# 150223_AriloRX_REV2_0_0.net
KiCad netlist of a schematic drawn in EAGLE
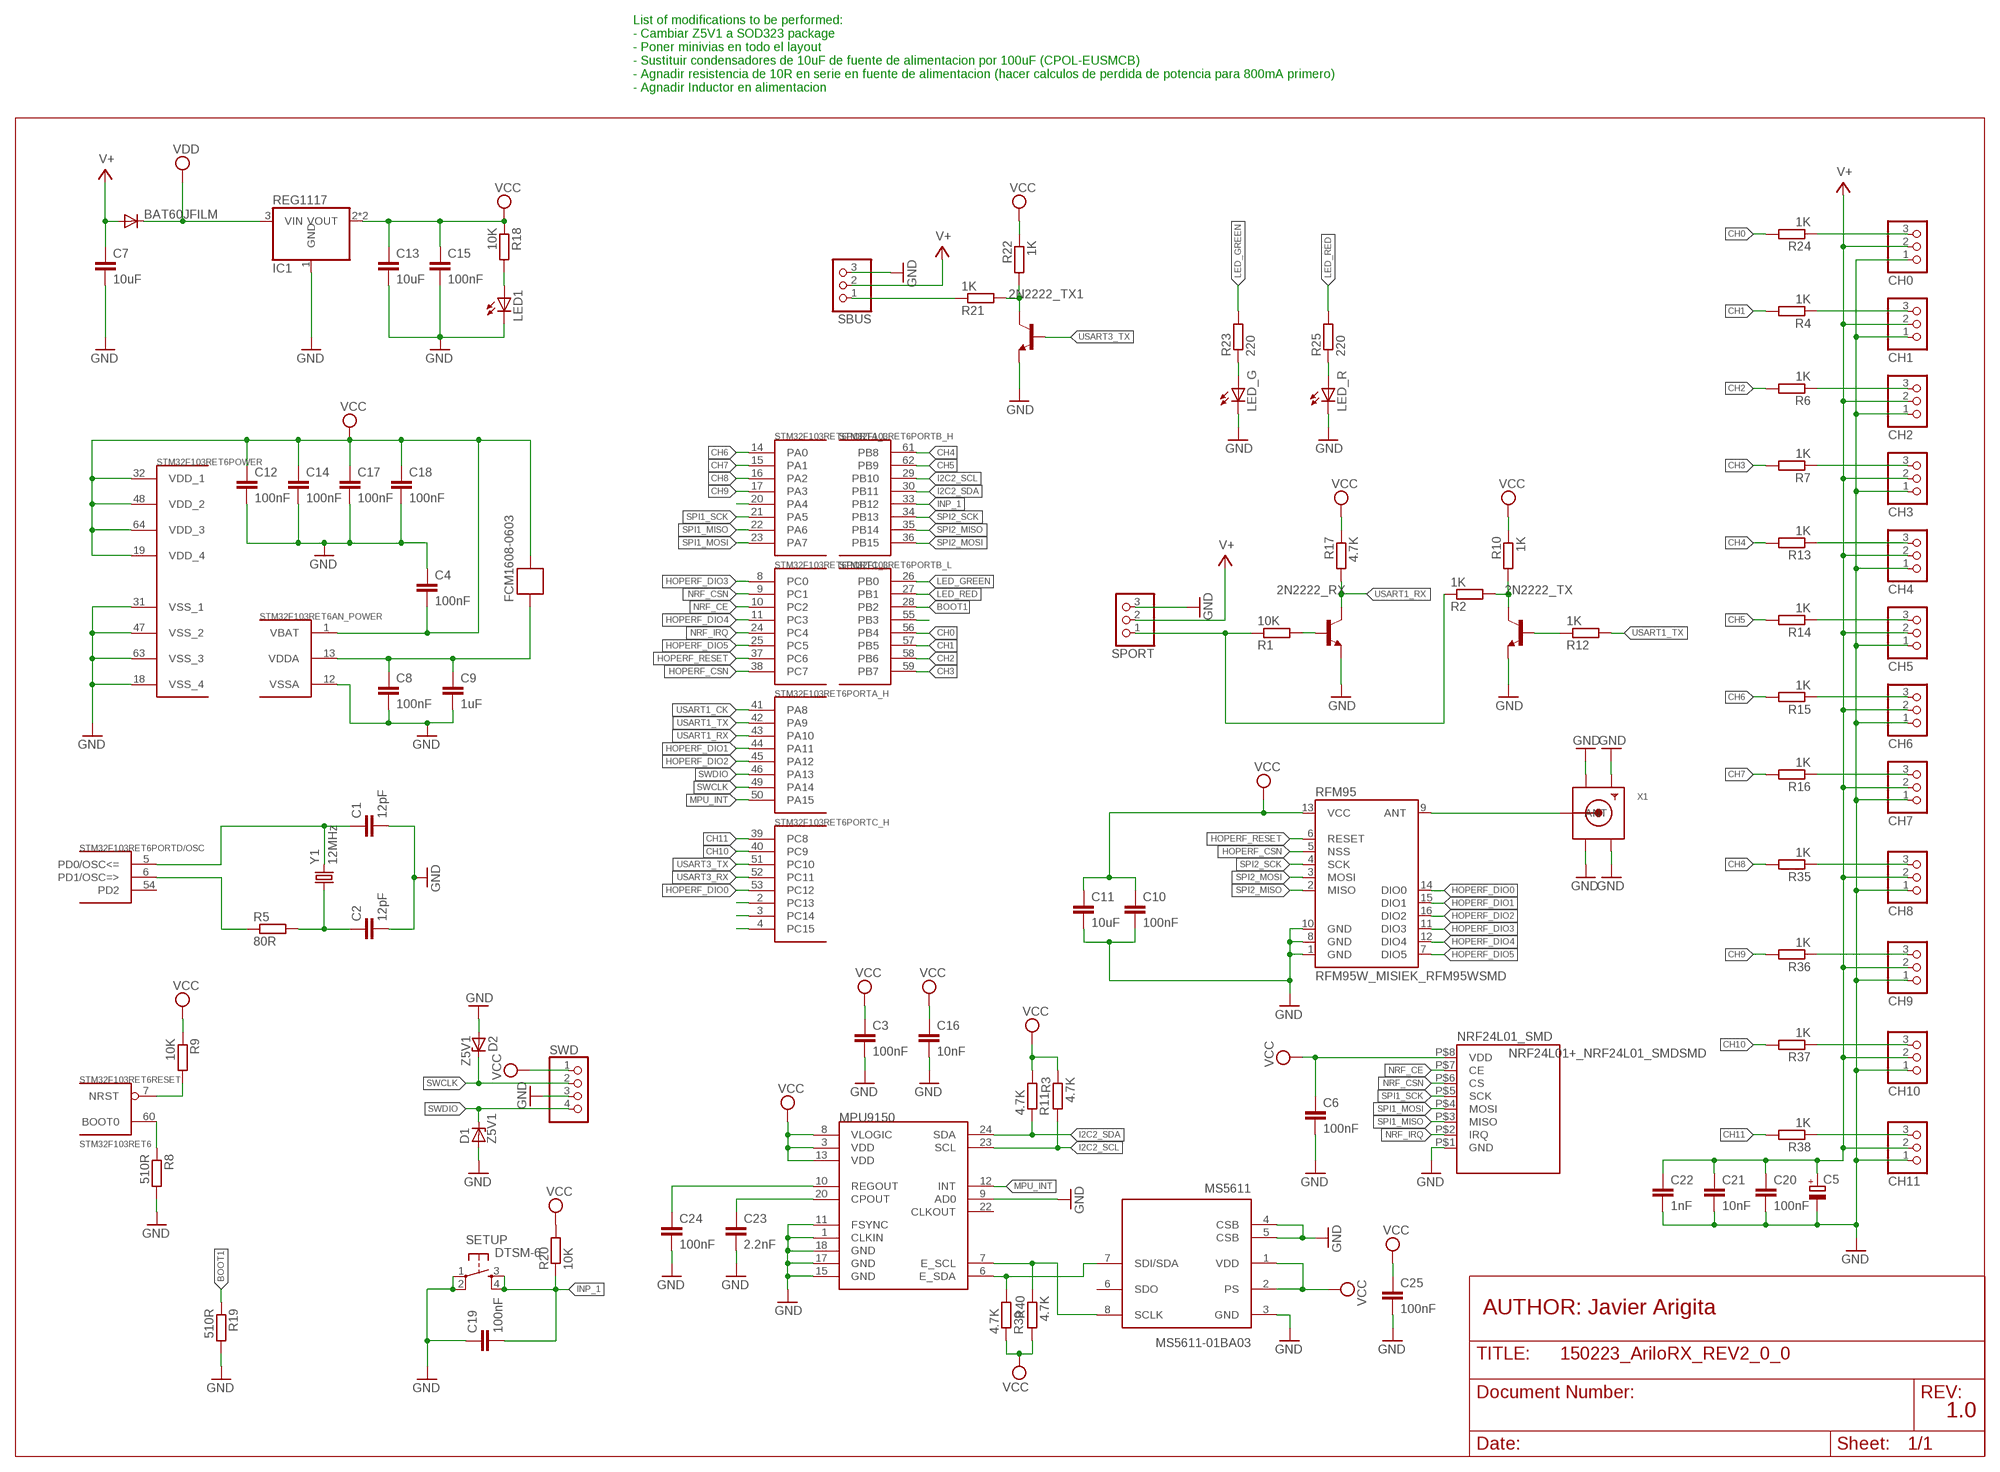
[diagram p0: schematic, sheet 1]

(export (version "E")
  (design (tool "Eeschema 10.0.6"))
  (components
    (comp (ref "2N2222_RX")
      (value "MMBT2222ALT1-NPN-SOT23-BEC")
      (footprint "eagle-import:SOT23-BEC")
      (libsource (lib "eagle-import") (part "-NPN-SOT23-BECMMBT2222ALT1"))
    )
    (comp (ref "2N2222_TX")
      (value "MMBT2222ALT1-NPN-SOT23-BEC")
      (footprint "eagle-import:SOT23-BEC")
      (libsource (lib "eagle-import") (part "-NPN-SOT23-BECMMBT2222ALT1"))
    )
    (comp (ref "2N2222_TX1")
      (value "MMBT2222ALT1-NPN-SOT23-BEC")
      (footprint "eagle-import:SOT23-BEC")
      (libsource (lib "eagle-import") (part "-NPN-SOT23-BECMMBT2222ALT1"))
    )
    (comp (ref "BAT60JFILM")
      (value "DIODE-SOD323-R")
      (footprint "eagle-import:SOD323-R")
      (libsource (lib "eagle-import") (part "DIODE-SOD323-R"))
    )
    (comp (ref "C1")
      (value "12pF")
      (footprint "eagle-import:RESISTOR_C0603")
      (libsource (lib "eagle-import") (part "RESISTOR_C-EUC0603"))
    )
    (comp (ref "C2")
      (value "12pF")
      (footprint "eagle-import:RESISTOR_C0603")
      (libsource (lib "eagle-import") (part "RESISTOR_C-EUC0603"))
    )
    (comp (ref "C3")
      (value "100nF")
      (footprint "eagle-import:RESISTOR_C0603")
      (libsource (lib "eagle-import") (part "RESISTOR_C-EUC0603"))
    )
    (comp (ref "C4")
      (value "100nF")
      (footprint "eagle-import:RESISTOR_C0603")
      (libsource (lib "eagle-import") (part "RESISTOR_C-EUC0603"))
    )
    (comp (ref "C5")
      (value "CPOL-EUSMCB")
      (footprint "eagle-import:SMC_B")
      (libsource (lib "eagle-import") (part "CPOL-EUSMCB"))
    )
    (comp (ref "C6")
      (value "100nF")
      (footprint "eagle-import:RESISTOR_C0603")
      (libsource (lib "eagle-import") (part "RESISTOR_C-EUC0603"))
    )
    (comp (ref "C7")
      (value "10uF")
      (footprint "eagle-import:RESISTOR_C3216")
      (libsource (lib "eagle-import") (part "RESISTOR_C-EUC3216"))
    )
    (comp (ref "C8")
      (value "100nF")
      (footprint "eagle-import:RESISTOR_C0603")
      (libsource (lib "eagle-import") (part "RESISTOR_C-EUC0603"))
    )
    (comp (ref "C9")
      (value "1uF")
      (footprint "eagle-import:RESISTOR_C0603")
      (libsource (lib "eagle-import") (part "RESISTOR_C-EUC0603"))
    )
    (comp (ref "C10")
      (value "100nF")
      (footprint "eagle-import:RESISTOR_C0603")
      (libsource (lib "eagle-import") (part "RESISTOR_C-EUC0603"))
    )
    (comp (ref "C11")
      (value "10uF")
      (footprint "eagle-import:RESISTOR_C3216")
      (libsource (lib "eagle-import") (part "RESISTOR_C-EUC3216"))
    )
    (comp (ref "C12")
      (value "100nF")
      (footprint "eagle-import:RESISTOR_C0603")
      (libsource (lib "eagle-import") (part "RESISTOR_C-EUC0603"))
    )
    (comp (ref "C13")
      (value "10uF")
      (footprint "eagle-import:RESISTOR_C3216")
      (libsource (lib "eagle-import") (part "RESISTOR_C-EUC3216"))
    )
    (comp (ref "C14")
      (value "100nF")
      (footprint "eagle-import:RESISTOR_C0603")
      (libsource (lib "eagle-import") (part "RESISTOR_C-EUC0603"))
    )
    (comp (ref "C15")
      (value "100nF")
      (footprint "eagle-import:RESISTOR_C0603")
      (libsource (lib "eagle-import") (part "RESISTOR_C-EUC0603"))
    )
    (comp (ref "C16")
      (value "10nF")
      (footprint "eagle-import:RESISTOR_C0603")
      (libsource (lib "eagle-import") (part "RESISTOR_C-EUC0603"))
    )
    (comp (ref "C17")
      (value "100nF")
      (footprint "eagle-import:RESISTOR_C0603")
      (libsource (lib "eagle-import") (part "RESISTOR_C-EUC0603"))
    )
    (comp (ref "C18")
      (value "100nF")
      (footprint "eagle-import:RESISTOR_C0603")
      (libsource (lib "eagle-import") (part "RESISTOR_C-EUC0603"))
    )
    (comp (ref "C19")
      (value "100nF")
      (footprint "eagle-import:RESISTOR_C0603")
      (libsource (lib "eagle-import") (part "RESISTOR_C-EUC0603"))
    )
    (comp (ref "C20")
      (value "100nF")
      (footprint "eagle-import:RESISTOR_C0603")
      (libsource (lib "eagle-import") (part "RESISTOR_C-EUC0603"))
    )
    (comp (ref "C21")
      (value "10nF")
      (footprint "eagle-import:RESISTOR_C0603")
      (libsource (lib "eagle-import") (part "RESISTOR_C-EUC0603"))
    )
    (comp (ref "C22")
      (value "1nF")
      (footprint "eagle-import:RESISTOR_C0603")
      (libsource (lib "eagle-import") (part "RESISTOR_C-EUC0603"))
    )
    (comp (ref "C23")
      (value "2.2nF")
      (footprint "eagle-import:RESISTOR_C0603")
      (libsource (lib "eagle-import") (part "RESISTOR_C-EUC0603"))
    )
    (comp (ref "C24")
      (value "100nF")
      (footprint "eagle-import:RESISTOR_C0603")
      (libsource (lib "eagle-import") (part "RESISTOR_C-EUC0603"))
    )
    (comp (ref "C25")
      (value "100nF")
      (footprint "eagle-import:RESISTOR_C0603")
      (libsource (lib "eagle-import") (part "RESISTOR_C-EUC0603"))
    )
    (comp (ref "CH0")
      (value "PINHD-1X3")
      (footprint "eagle-import:1X03")
      (libsource (lib "eagle-import") (part "PINHD-1X3"))
    )
    (comp (ref "CH1")
      (value "PINHD-1X3")
      (footprint "eagle-import:1X03")
      (libsource (lib "eagle-import") (part "PINHD-1X3"))
    )
    (comp (ref "CH2")
      (value "PINHD-1X3")
      (footprint "eagle-import:1X03")
      (libsource (lib "eagle-import") (part "PINHD-1X3"))
    )
    (comp (ref "CH3")
      (value "PINHD-1X3")
      (footprint "eagle-import:1X03")
      (libsource (lib "eagle-import") (part "PINHD-1X3"))
    )
    (comp (ref "CH4")
      (value "PINHD-1X3")
      (footprint "eagle-import:1X03")
      (libsource (lib "eagle-import") (part "PINHD-1X3"))
    )
    (comp (ref "CH5")
      (value "PINHD-1X3")
      (footprint "eagle-import:1X03")
      (libsource (lib "eagle-import") (part "PINHD-1X3"))
    )
    (comp (ref "CH6")
      (value "PINHD-1X3")
      (footprint "eagle-import:1X03")
      (libsource (lib "eagle-import") (part "PINHD-1X3"))
    )
    (comp (ref "CH7")
      (value "PINHD-1X3")
      (footprint "eagle-import:1X03")
      (libsource (lib "eagle-import") (part "PINHD-1X3"))
    )
    (comp (ref "CH8")
      (value "PINHD-1X3")
      (footprint "eagle-import:1X03")
      (libsource (lib "eagle-import") (part "PINHD-1X3"))
    )
    (comp (ref "CH9")
      (value "PINHD-1X3")
      (footprint "eagle-import:1X03")
      (libsource (lib "eagle-import") (part "PINHD-1X3"))
    )
    (comp (ref "CH10")
      (value "PINHD-1X3")
      (footprint "eagle-import:1X03")
      (libsource (lib "eagle-import") (part "PINHD-1X3"))
    )
    (comp (ref "CH11")
      (value "PINHD-1X3")
      (footprint "eagle-import:1X03")
      (libsource (lib "eagle-import") (part "PINHD-1X3"))
    )
    (comp (ref "D1")
      (value "Z5V1")
      (footprint "eagle-import:SOD80C")
      (libsource (lib "eagle-import") (part "ZENER-DIODESOD80C"))
    )
    (comp (ref "D2")
      (value "Z5V1")
      (footprint "eagle-import:SOD80C")
      (libsource (lib "eagle-import") (part "ZENER-DIODESOD80C"))
    )
    (comp (ref "FCM1608-0603")
      (value "FERRITE-BEAD")
      (footprint "eagle-import:R0603")
      (libsource (lib "eagle-import") (part "FERRITE-BEAD"))
    )
    (comp (ref "IC1")
      (value "REG1117")
      (footprint "eagle-import:SOT223")
      (libsource (lib "eagle-import") (part "REG1117"))
    )
    (comp (ref "LED1")
      (value "LED_LEDCHIP-LED0603")
      (footprint "eagle-import:LED_CHIP-LED0603")
      (libsource (lib "eagle-import") (part "LED_LEDCHIP-LED0603"))
    )
    (comp (ref "LED_G")
      (value "LEDCHIP-LED0603")
      (footprint "eagle-import:CHIP-LED0603")
      (libsource (lib "eagle-import") (part "LEDCHIP-LED0603"))
    )
    (comp (ref "LED_R")
      (value "LEDCHIP-LED0603")
      (footprint "eagle-import:CHIP-LED0603")
      (libsource (lib "eagle-import") (part "LEDCHIP-LED0603"))
    )
    (comp (ref "MPU9150")
      (value "MPU-9150QFN-24-NP")
      (footprint "eagle-import:QFN-24-NP")
      (libsource (lib "eagle-import") (part "MPU-9150QFN-24-NP"))
    )
    (comp (ref "MS5611")
      (value "MS5611-01BA03")
      (footprint "eagle-import:SON125P300X500X100-8N")
      (libsource (lib "eagle-import") (part "MS5611-01BA03"))
    )
    (comp (ref "NRF24L01_SMD")
      (value "NRF24L01+_NRF24L01_SMDSMD")
      (footprint "eagle-import:NRF24L01+_NRF24L01_SMD")
      (libsource (lib "eagle-import") (part "NRF24L01+_NRF24L01_SMDSMD"))
    )
    (comp (ref "R1")
      (value "10K")
      (footprint "eagle-import:RCL_R0603")
      (libsource (lib "eagle-import") (part "RCL_R-EU_R0603"))
    )
    (comp (ref "R2")
      (value "1K")
      (footprint "eagle-import:RCL_R0603")
      (libsource (lib "eagle-import") (part "RCL_R-EU_R0603"))
    )
    (comp (ref "R3")
      (value "4.7K")
      (footprint "eagle-import:RCL_R0603")
      (libsource (lib "eagle-import") (part "RCL_R-EU_R0603"))
    )
    (comp (ref "R4")
      (value "1K")
      (footprint "eagle-import:RCL_R0603")
      (libsource (lib "eagle-import") (part "RCL_R-EU_R0603"))
    )
    (comp (ref "R5")
      (value "80R")
      (footprint "eagle-import:RCL_R0603")
      (libsource (lib "eagle-import") (part "RCL_R-EU_R0603"))
    )
    (comp (ref "R6")
      (value "1K")
      (footprint "eagle-import:RCL_R0603")
      (libsource (lib "eagle-import") (part "RCL_R-EU_R0603"))
    )
    (comp (ref "R7")
      (value "1K")
      (footprint "eagle-import:RCL_R0603")
      (libsource (lib "eagle-import") (part "RCL_R-EU_R0603"))
    )
    (comp (ref "R8")
      (value "510R")
      (footprint "eagle-import:RCL_R0603")
      (libsource (lib "eagle-import") (part "RCL_R-EU_R0603"))
    )
    (comp (ref "R9")
      (value "10K")
      (footprint "eagle-import:RCL_R0603")
      (libsource (lib "eagle-import") (part "RCL_R-EU_R0603"))
    )
    (comp (ref "R10")
      (value "1K")
      (footprint "eagle-import:RCL_R0603")
      (libsource (lib "eagle-import") (part "RCL_R-EU_R0603"))
    )
    (comp (ref "R11")
      (value "4.7K")
      (footprint "eagle-import:RCL_R0603")
      (libsource (lib "eagle-import") (part "RCL_R-EU_R0603"))
    )
    (comp (ref "R12")
      (value "1K")
      (footprint "eagle-import:RCL_R0603")
      (libsource (lib "eagle-import") (part "RCL_R-EU_R0603"))
    )
    (comp (ref "R13")
      (value "1K")
      (footprint "eagle-import:RCL_R0603")
      (libsource (lib "eagle-import") (part "RCL_R-EU_R0603"))
    )
    (comp (ref "R14")
      (value "1K")
      (footprint "eagle-import:RCL_R0603")
      (libsource (lib "eagle-import") (part "RCL_R-EU_R0603"))
    )
    (comp (ref "R15")
      (value "1K")
      (footprint "eagle-import:RCL_R0603")
      (libsource (lib "eagle-import") (part "RCL_R-EU_R0603"))
    )
    (comp (ref "R16")
      (value "1K")
      (footprint "eagle-import:RCL_R0603")
      (libsource (lib "eagle-import") (part "RCL_R-EU_R0603"))
    )
    (comp (ref "R17")
      (value "4.7K")
      (footprint "eagle-import:RCL_R0603")
      (libsource (lib "eagle-import") (part "RCL_R-EU_R0603"))
    )
    (comp (ref "R18")
      (value "10K")
      (footprint "eagle-import:RCL_R0603")
      (libsource (lib "eagle-import") (part "RCL_R-EU_R0603"))
    )
    (comp (ref "R19")
      (value "510R")
      (footprint "eagle-import:RCL_R0603")
      (libsource (lib "eagle-import") (part "RCL_R-EU_R0603"))
    )
    (comp (ref "R20")
      (value "10K")
      (footprint "eagle-import:RCL_R0603")
      (libsource (lib "eagle-import") (part "RCL_R-EU_R0603"))
    )
    (comp (ref "R21")
      (value "1K")
      (footprint "eagle-import:RCL_R0603")
      (libsource (lib "eagle-import") (part "RCL_R-EU_R0603"))
    )
    (comp (ref "R22")
      (value "1K")
      (footprint "eagle-import:RCL_R0603")
      (libsource (lib "eagle-import") (part "RCL_R-EU_R0603"))
    )
    (comp (ref "R23")
      (value "220")
      (footprint "eagle-import:RCL_R0603")
      (libsource (lib "eagle-import") (part "RCL_R-EU_R0603"))
    )
    (comp (ref "R24")
      (value "1K")
      (footprint "eagle-import:RCL_R0603")
      (libsource (lib "eagle-import") (part "RCL_R-EU_R0603"))
    )
    (comp (ref "R25")
      (value "220")
      (footprint "eagle-import:RCL_R0603")
      (libsource (lib "eagle-import") (part "RCL_R-EU_R0603"))
    )
    (comp (ref "R35")
      (value "1K")
      (footprint "eagle-import:RCL_R0603")
      (libsource (lib "eagle-import") (part "RCL_R-EU_R0603"))
    )
    (comp (ref "R36")
      (value "1K")
      (footprint "eagle-import:RCL_R0603")
      (libsource (lib "eagle-import") (part "RCL_R-EU_R0603"))
    )
    (comp (ref "R37")
      (value "1K")
      (footprint "eagle-import:RCL_R0603")
      (libsource (lib "eagle-import") (part "RCL_R-EU_R0603"))
    )
    (comp (ref "R38")
      (value "1K")
      (footprint "eagle-import:RCL_R0603")
      (libsource (lib "eagle-import") (part "RCL_R-EU_R0603"))
    )
    (comp (ref "R39")
      (value "4.7K")
      (footprint "eagle-import:RCL_R0603")
      (libsource (lib "eagle-import") (part "RCL_R-EU_R0603"))
    )
    (comp (ref "R40")
      (value "4.7K")
      (footprint "eagle-import:RCL_R0603")
      (libsource (lib "eagle-import") (part "RCL_R-EU_R0603"))
    )
    (comp (ref "RFM95")
      (value "RFM95W_MISIEK_RFM95WSMD")
      (footprint "eagle-import:RFM95W_MISIEK_RFM95W_SMD")
      (libsource (lib "eagle-import") (part "RFM95W_MISIEK_RFM95WSMD"))
    )
    (comp (ref "SBUS")
      (value "PINHD-1X3")
      (footprint "eagle-import:1X03")
      (libsource (lib "eagle-import") (part "PINHD-1X3"))
    )
    (comp (ref "SETUP")
      (value "DTSM-6")
      (footprint "eagle-import:DTSM-6")
      (libsource (lib "eagle-import") (part "DTSM-6"))
    )
    (comp (ref "SPORT")
      (value "PINHD-1X3")
      (footprint "eagle-import:1X03")
      (libsource (lib "eagle-import") (part "PINHD-1X3"))
    )
    (comp (ref "STM32F103RET6")
      (value "STM32F103RET6")
      (footprint "eagle-import:TQFP64")
      (libsource (lib "eagle-import") (part "STM32F10XRXT6"))
    )
    (comp (ref "SWD")
      (value "PINHD-1X4")
      (footprint "eagle-import:1X04")
      (libsource (lib "eagle-import") (part "PINHD-1X4"))
    )
    (comp (ref "X1")
      (value "SMACONNECTOR_EDGE")
      (footprint "eagle-import:SMA_EDGELAUNCH")
      (libsource (lib "eagle-import") (part "SMACONNECTOR_EDGE"))
    )
    (comp (ref "Y1")
      (value "12MHz")
      (footprint "eagle-import:CRYSTAL-SMD-5X3")
      (libsource (lib "eagle-import") (part "CRYSTAL5X3"))
    )
  )
  (nets
    (net (code "1") (name "BOOT1") (class "Default")
      (node (ref "R19") (pin "1") (pinfunction "1_1") (pintype "passive"))
      (node (ref "STM32F103RET6") (pin "28") (pinfunction "PB2_28") (pintype "bidirectional"))
    )
    (net (code "2") (name "CH0") (class "Default")
      (node (ref "R24") (pin "2") (pinfunction "2_2") (pintype "passive"))
      (node (ref "STM32F103RET6") (pin "56") (pinfunction "PB4_56") (pintype "bidirectional"))
    )
    (net (code "3") (name "CH1") (class "Default")
      (node (ref "R4") (pin "2") (pinfunction "2_2") (pintype "passive"))
      (node (ref "STM32F103RET6") (pin "57") (pinfunction "PB5_57") (pintype "bidirectional"))
    )
    (net (code "4") (name "CH2") (class "Default")
      (node (ref "R6") (pin "2") (pinfunction "2_2") (pintype "passive"))
      (node (ref "STM32F103RET6") (pin "58") (pinfunction "PB6_58") (pintype "bidirectional"))
    )
    (net (code "5") (name "CH3") (class "Default")
      (node (ref "R7") (pin "2") (pinfunction "2_2") (pintype "passive"))
      (node (ref "STM32F103RET6") (pin "59") (pinfunction "PB7_59") (pintype "bidirectional"))
    )
    (net (code "6") (name "CH4") (class "Default")
      (node (ref "R13") (pin "2") (pinfunction "2_2") (pintype "passive"))
      (node (ref "STM32F103RET6") (pin "61") (pinfunction "PB8_61") (pintype "bidirectional"))
    )
    (net (code "7") (name "CH5") (class "Default")
      (node (ref "R14") (pin "2") (pinfunction "2_2") (pintype "passive"))
      (node (ref "STM32F103RET6") (pin "62") (pinfunction "PB9_62") (pintype "bidirectional"))
    )
    (net (code "8") (name "CH6") (class "Default")
      (node (ref "R15") (pin "2") (pinfunction "2_2") (pintype "passive"))
      (node (ref "STM32F103RET6") (pin "14") (pinfunction "PA0_14") (pintype "bidirectional"))
    )
    (net (code "9") (name "CH7") (class "Default")
      (node (ref "R16") (pin "2") (pinfunction "2_2") (pintype "passive"))
      (node (ref "STM32F103RET6") (pin "15") (pinfunction "PA1_15") (pintype "bidirectional"))
    )
    (net (code "10") (name "CH8") (class "Default")
      (node (ref "R35") (pin "2") (pinfunction "2_2") (pintype "passive"))
      (node (ref "STM32F103RET6") (pin "16") (pinfunction "PA2_16") (pintype "bidirectional"))
    )
    (net (code "11") (name "CH9") (class "Default")
      (node (ref "R36") (pin "2") (pinfunction "2_2") (pintype "passive"))
      (node (ref "STM32F103RET6") (pin "17") (pinfunction "PA3_17") (pintype "bidirectional"))
    )
    (net (code "12") (name "CH10") (class "Default")
      (node (ref "R37") (pin "2") (pinfunction "2_2") (pintype "passive"))
      (node (ref "STM32F103RET6") (pin "40") (pinfunction "PC9_40") (pintype "bidirectional"))
    )
    (net (code "13") (name "CH11") (class "Default")
      (node (ref "R38") (pin "2") (pinfunction "2_2") (pintype "passive"))
      (node (ref "STM32F103RET6") (pin "39") (pinfunction "PC8_39") (pintype "bidirectional"))
    )
    (net (code "14") (name "GND") (class "Default")
      (node (ref "2N2222_RX") (pin "E") (pinfunction "E_E") (pintype "passive"))
      (node (ref "2N2222_TX") (pin "E") (pinfunction "E_E") (pintype "passive"))
      (node (ref "2N2222_TX1") (pin "E") (pinfunction "E_E") (pintype "passive"))
      (node (ref "C1") (pin "2") (pinfunction "2_2") (pintype "passive"))
      (node (ref "C10") (pin "2") (pinfunction "2_2") (pintype "passive"))
      (node (ref "C11") (pin "2") (pinfunction "2_2") (pintype "passive"))
      (node (ref "C12") (pin "2") (pinfunction "2_2") (pintype "passive"))
      (node (ref "C13") (pin "2") (pinfunction "2_2") (pintype "passive"))
      (node (ref "C14") (pin "2") (pinfunction "2_2") (pintype "passive"))
      (node (ref "C15") (pin "2") (pinfunction "2_2") (pintype "passive"))
      (node (ref "C16") (pin "2") (pinfunction "2_2") (pintype "passive"))
      (node (ref "C17") (pin "2") (pinfunction "2_2") (pintype "passive"))
      (node (ref "C18") (pin "2") (pinfunction "2_2") (pintype "passive"))
      (node (ref "C19") (pin "1") (pinfunction "1_1") (pintype "passive"))
      (node (ref "C2") (pin "2") (pinfunction "2_2") (pintype "passive"))
      (node (ref "C20") (pin "2") (pinfunction "2_2") (pintype "passive"))
      (node (ref "C21") (pin "2") (pinfunction "2_2") (pintype "passive"))
      (node (ref "C22") (pin "2") (pinfunction "2_2") (pintype "passive"))
      (node (ref "C23") (pin "2") (pinfunction "2_2") (pintype "passive"))
      (node (ref "C24") (pin "2") (pinfunction "2_2") (pintype "passive"))
      (node (ref "C25") (pin "2") (pinfunction "2_2") (pintype "passive"))
      (node (ref "C3") (pin "2") (pinfunction "2_2") (pintype "passive"))
      (node (ref "C4") (pin "1") (pinfunction "1_1") (pintype "passive"))
      (node (ref "C5") (pin "-") (pinfunction "-_-") (pintype "passive"))
      (node (ref "C6") (pin "2") (pinfunction "2_2") (pintype "passive"))
      (node (ref "C7") (pin "2") (pinfunction "2_2") (pintype "passive"))
      (node (ref "C8") (pin "2") (pinfunction "2_2") (pintype "passive"))
      (node (ref "C9") (pin "2") (pinfunction "2_2") (pintype "passive"))
      (node (ref "CH0") (pin "1") (pinfunction "1_1") (pintype "passive"))
      (node (ref "CH1") (pin "1") (pinfunction "1_1") (pintype "passive"))
      (node (ref "CH10") (pin "1") (pinfunction "1_1") (pintype "passive"))
      (node (ref "CH11") (pin "1") (pinfunction "1_1") (pintype "passive"))
      (node (ref "CH2") (pin "1") (pinfunction "1_1") (pintype "passive"))
      (node (ref "CH3") (pin "1") (pinfunction "1_1") (pintype "passive"))
      (node (ref "CH4") (pin "1") (pinfunction "1_1") (pintype "passive"))
      (node (ref "CH5") (pin "1") (pinfunction "1_1") (pintype "passive"))
      (node (ref "CH6") (pin "1") (pinfunction "1_1") (pintype "passive"))
      (node (ref "CH7") (pin "1") (pinfunction "1_1") (pintype "passive"))
      (node (ref "CH8") (pin "1") (pinfunction "1_1") (pintype "passive"))
      (node (ref "CH9") (pin "1") (pinfunction "1_1") (pintype "passive"))
      (node (ref "D1") (pin "A") (pinfunction "A_A") (pintype "passive"))
      (node (ref "D2") (pin "A") (pinfunction "A_A") (pintype "passive"))
      (node (ref "IC1") (pin "1") (pinfunction "GND_1") (pintype "power_in"))
      (node (ref "LED1") (pin "C") (pinfunction "C_C") (pintype "passive"))
      (node (ref "LED_G") (pin "C") (pinfunction "C_C") (pintype "passive"))
      (node (ref "LED_R") (pin "C") (pinfunction "C_C") (pintype "passive"))
      (node (ref "MPU9150") (pin "1") (pinfunction "CLKIN_1") (pintype "bidirectional"))
      (node (ref "MPU9150") (pin "11") (pinfunction "FSYNC_11") (pintype "bidirectional"))
      (node (ref "MPU9150") (pin "15") (pinfunction "GND_15") (pintype "bidirectional"))
      (node (ref "MPU9150") (pin "17") (pinfunction "GND_17") (pintype "bidirectional"))
      (node (ref "MPU9150") (pin "18") (pinfunction "GND_18") (pintype "bidirectional"))
      (node (ref "MPU9150") (pin "9") (pinfunction "AD0_9") (pintype "bidirectional"))
      (node (ref "MS5611") (pin "3") (pinfunction "GND_3") (pintype "power_in"))
      (node (ref "MS5611") (pin "4") (pinfunction "CSB_4") (pintype "input"))
      (node (ref "MS5611") (pin "5") (pinfunction "CSB_5") (pintype "input"))
      (node (ref "NRF24L01_SMD") (pin "P$1") (pinfunction "GND_P$1") (pintype "power_in"))
      (node (ref "R19") (pin "2") (pinfunction "2_2") (pintype "passive"))
      (node (ref "R8") (pin "2") (pinfunction "2_2") (pintype "passive"))
      (node (ref "RFM95") (pin "1") (pinfunction "GND_1") (pintype "power_in"))
      (node (ref "RFM95") (pin "10") (pinfunction "GND_10") (pintype "power_in"))
      (node (ref "RFM95") (pin "8") (pinfunction "GND_8") (pintype "power_in"))
      (node (ref "SBUS") (pin "3") (pinfunction "3_3") (pintype "passive"))
      (node (ref "SETUP") (pin "1") (pinfunction "1_1") (pintype "passive"))
      (node (ref "SETUP") (pin "2") (pinfunction "2_2") (pintype "passive"))
      (node (ref "SPORT") (pin "3") (pinfunction "3_3") (pintype "passive"))
      (node (ref "STM32F103RET6") (pin "12") (pinfunction "VSSA_12") (pintype "power_in"))
      (node (ref "STM32F103RET6") (pin "18") (pinfunction "VSS_4_18") (pintype "power_in"))
      (node (ref "STM32F103RET6") (pin "31") (pinfunction "VSS_1_31") (pintype "power_in"))
      (node (ref "STM32F103RET6") (pin "47") (pinfunction "VSS_2_47") (pintype "power_in"))
      (node (ref "STM32F103RET6") (pin "63") (pinfunction "VSS_3_63") (pintype "power_in"))
      (node (ref "SWD") (pin "3") (pinfunction "3_3") (pintype "passive"))
      (node (ref "X1") (pin "GND@1") (pinfunction "GND4_GND@1") (pintype "power_in"))
      (node (ref "X1") (pin "GND@2") (pinfunction "GND3_GND@2") (pintype "power_in"))
      (node (ref "X1") (pin "GND@3") (pinfunction "GND2_GND@3") (pintype "power_in"))
      (node (ref "X1") (pin "GND@4") (pinfunction "GND1_GND@4") (pintype "power_in"))
    )
    (net (code "15") (name "HOPERF_CSN") (class "Default")
      (node (ref "RFM95") (pin "5") (pinfunction "NSS_5") (pintype "input"))
      (node (ref "STM32F103RET6") (pin "38") (pinfunction "PC7_38") (pintype "bidirectional"))
    )
    (net (code "16") (name "HOPERF_DIO0") (class "Default")
      (node (ref "RFM95") (pin "14") (pinfunction "DIO0_14") (pintype "input"))
      (node (ref "STM32F103RET6") (pin "53") (pinfunction "PC12_53") (pintype "bidirectional"))
    )
    (net (code "17") (name "HOPERF_DIO1") (class "Default")
      (node (ref "RFM95") (pin "15") (pinfunction "DIO1_15") (pintype "input"))
      (node (ref "STM32F103RET6") (pin "44") (pinfunction "PA11_44") (pintype "bidirectional"))
    )
    (net (code "18") (name "HOPERF_DIO2") (class "Default")
      (node (ref "RFM95") (pin "16") (pinfunction "DIO2_16") (pintype "input"))
      (node (ref "STM32F103RET6") (pin "45") (pinfunction "PA12_45") (pintype "bidirectional"))
    )
    (net (code "19") (name "HOPERF_DIO3") (class "Default")
      (node (ref "RFM95") (pin "11") (pinfunction "DIO3_11") (pintype "bidirectional"))
      (node (ref "STM32F103RET6") (pin "8") (pinfunction "PC0_8") (pintype "bidirectional"))
    )
    (net (code "20") (name "HOPERF_DIO4") (class "Default")
      (node (ref "RFM95") (pin "12") (pinfunction "DIO4_12") (pintype "bidirectional"))
      (node (ref "STM32F103RET6") (pin "11") (pinfunction "PC3_11") (pintype "bidirectional"))
    )
    (net (code "21") (name "HOPERF_DIO5") (class "Default")
      (node (ref "RFM95") (pin "7") (pinfunction "DIO5_7") (pintype "bidirectional"))
      (node (ref "STM32F103RET6") (pin "25") (pinfunction "PC5_25") (pintype "bidirectional"))
    )
    (net (code "22") (name "HOPERF_RESET") (class "Default")
      (node (ref "RFM95") (pin "6") (pinfunction "RESET_6") (pintype "output"))
      (node (ref "STM32F103RET6") (pin "37") (pinfunction "PC6_37") (pintype "bidirectional"))
    )
    (net (code "23") (name "I2C2_SCL") (class "Default")
      (node (ref "MPU9150") (pin "23") (pinfunction "SCL_23") (pintype "bidirectional"))
      (node (ref "R3") (pin "2") (pinfunction "2_2") (pintype "passive"))
      (node (ref "STM32F103RET6") (pin "29") (pinfunction "PB10_29") (pintype "bidirectional"))
    )
    (net (code "24") (name "I2C2_SDA") (class "Default")
      (node (ref "MPU9150") (pin "24") (pinfunction "SDA_24") (pintype "bidirectional"))
      (node (ref "R11") (pin "1") (pinfunction "1_1") (pintype "passive"))
      (node (ref "STM32F103RET6") (pin "30") (pinfunction "PB11_30") (pintype "bidirectional"))
    )
    (net (code "25") (name "INP_1") (class "Default")
      (node (ref "C19") (pin "2") (pinfunction "2_2") (pintype "passive"))
      (node (ref "R20") (pin "1") (pinfunction "1_1") (pintype "passive"))
      (node (ref "SETUP") (pin "3") (pinfunction "3_3") (pintype "passive"))
      (node (ref "SETUP") (pin "4") (pinfunction "4_4") (pintype "passive"))
      (node (ref "STM32F103RET6") (pin "33") (pinfunction "PB12_33") (pintype "bidirectional"))
    )
    (net (code "26") (name "LED_GREEN") (class "Default")
      (node (ref "R23") (pin "2") (pinfunction "2_2") (pintype "passive"))
      (node (ref "STM32F103RET6") (pin "26") (pinfunction "PB0_26") (pintype "bidirectional"))
    )
    (net (code "27") (name "LED_RED") (class "Default")
      (node (ref "R25") (pin "2") (pinfunction "2_2") (pintype "passive"))
      (node (ref "STM32F103RET6") (pin "27") (pinfunction "PB1_27") (pintype "bidirectional"))
    )
    (net (code "28") (name "MPU_INT") (class "Default")
      (node (ref "MPU9150") (pin "12") (pinfunction "INT_12") (pintype "bidirectional"))
      (node (ref "STM32F103RET6") (pin "50") (pinfunction "PA15_50") (pintype "bidirectional"))
    )
    (net (code "29") (name "NRF_CE") (class "Default")
      (node (ref "NRF24L01_SMD") (pin "P$7") (pinfunction "CE_P$7") (pintype "input"))
      (node (ref "STM32F103RET6") (pin "10") (pinfunction "PC2_10") (pintype "bidirectional"))
    )
    (net (code "30") (name "NRF_CSN") (class "Default")
      (node (ref "NRF24L01_SMD") (pin "P$6") (pinfunction "CS_P$6") (pintype "input"))
      (node (ref "STM32F103RET6") (pin "9") (pinfunction "PC1_9") (pintype "bidirectional"))
    )
    (net (code "31") (name "NRF_IRQ") (class "Default")
      (node (ref "NRF24L01_SMD") (pin "P$2") (pinfunction "IRQ_P$2") (pintype "output"))
      (node (ref "STM32F103RET6") (pin "24") (pinfunction "PC4_24") (pintype "bidirectional"))
    )
    (net (code "32") (name "Net-(2N2222_RX-PadB)") (class "Default")
      (node (ref "2N2222_RX") (pin "B") (pinfunction "B_B") (pintype "passive"))
      (node (ref "R1") (pin "2") (pinfunction "2_2") (pintype "passive"))
    )
    (net (code "33") (name "Net-(2N2222_TX-PadB)") (class "Default")
      (node (ref "2N2222_TX") (pin "B") (pinfunction "B_B") (pintype "passive"))
      (node (ref "R12") (pin "1") (pinfunction "1_1") (pintype "passive"))
    )
    (net (code "34") (name "Net-(2N2222_TX-PadC)") (class "Default")
      (node (ref "2N2222_TX") (pin "C") (pinfunction "C_C") (pintype "passive"))
      (node (ref "R10") (pin "2") (pinfunction "2_2") (pintype "passive"))
      (node (ref "R2") (pin "2") (pinfunction "2_2") (pintype "passive"))
    )
    (net (code "35") (name "Net-(2N2222_TX1-PadC)") (class "Default")
      (node (ref "2N2222_TX1") (pin "C") (pinfunction "C_C") (pintype "passive"))
      (node (ref "R21") (pin "2") (pinfunction "2_2") (pintype "passive"))
      (node (ref "R22") (pin "2") (pinfunction "2_2") (pintype "passive"))
    )
    (net (code "36") (name "Net-(C2-Pad1)") (class "Default")
      (node (ref "C2") (pin "1") (pinfunction "1_1") (pintype "passive"))
      (node (ref "R5") (pin "2") (pinfunction "2_2") (pintype "passive"))
      (node (ref "Y1") (pin "1") (pinfunction "1_1") (pintype "passive"))
    )
    (net (code "37") (name "Net-(CH0-Pad3)") (class "Default")
      (node (ref "CH0") (pin "3") (pinfunction "3_3") (pintype "passive"))
      (node (ref "R24") (pin "1") (pinfunction "1_1") (pintype "passive"))
    )
    (net (code "38") (name "Net-(CH1-Pad3)") (class "Default")
      (node (ref "CH1") (pin "3") (pinfunction "3_3") (pintype "passive"))
      (node (ref "R4") (pin "1") (pinfunction "1_1") (pintype "passive"))
    )
    (net (code "39") (name "Net-(CH2-Pad3)") (class "Default")
      (node (ref "CH2") (pin "3") (pinfunction "3_3") (pintype "passive"))
      (node (ref "R6") (pin "1") (pinfunction "1_1") (pintype "passive"))
    )
    (net (code "40") (name "Net-(CH3-Pad3)") (class "Default")
      (node (ref "CH3") (pin "3") (pinfunction "3_3") (pintype "passive"))
      (node (ref "R7") (pin "1") (pinfunction "1_1") (pintype "passive"))
    )
    (net (code "41") (name "Net-(CH4-Pad3)") (class "Default")
      (node (ref "CH4") (pin "3") (pinfunction "3_3") (pintype "passive"))
      (node (ref "R13") (pin "1") (pinfunction "1_1") (pintype "passive"))
    )
    (net (code "42") (name "Net-(CH5-Pad3)") (class "Default")
      (node (ref "CH5") (pin "3") (pinfunction "3_3") (pintype "passive"))
      (node (ref "R14") (pin "1") (pinfunction "1_1") (pintype "passive"))
    )
    (net (code "43") (name "Net-(CH6-Pad3)") (class "Default")
      (node (ref "CH6") (pin "3") (pinfunction "3_3") (pintype "passive"))
      (node (ref "R15") (pin "1") (pinfunction "1_1") (pintype "passive"))
    )
    (net (code "44") (name "Net-(CH7-Pad3)") (class "Default")
      (node (ref "CH7") (pin "3") (pinfunction "3_3") (pintype "passive"))
      (node (ref "R16") (pin "1") (pinfunction "1_1") (pintype "passive"))
    )
    (net (code "45") (name "Net-(CH8-Pad3)") (class "Default")
      (node (ref "CH8") (pin "3") (pinfunction "3_3") (pintype "passive"))
      (node (ref "R35") (pin "1") (pinfunction "1_1") (pintype "passive"))
    )
    (net (code "46") (name "Net-(CH9-Pad3)") (class "Default")
      (node (ref "CH9") (pin "3") (pinfunction "3_3") (pintype "passive"))
      (node (ref "R36") (pin "1") (pinfunction "1_1") (pintype "passive"))
    )
    (net (code "47") (name "Net-(CH10-Pad3)") (class "Default")
      (node (ref "CH10") (pin "3") (pinfunction "3_3") (pintype "passive"))
      (node (ref "R37") (pin "1") (pinfunction "1_1") (pintype "passive"))
    )
    (net (code "48") (name "Net-(CH11-Pad3)") (class "Default")
      (node (ref "CH11") (pin "3") (pinfunction "3_3") (pintype "passive"))
      (node (ref "R38") (pin "1") (pinfunction "1_1") (pintype "passive"))
    )
    (net (code "49") (name "Net-(FCM1608-0603-P$2)") (class "Default")
      (node (ref "C8") (pin "1") (pinfunction "1_1") (pintype "passive"))
      (node (ref "C9") (pin "1") (pinfunction "1_1") (pintype "passive"))
      (node (ref "FCM1608-0603") (pin "2") (pinfunction "P$2_2") (pintype "bidirectional"))
      (node (ref "STM32F103RET6") (pin "13") (pinfunction "VDDA_13") (pintype "power_in"))
    )
    (net (code "50") (name "Net-(LED1-PadA)") (class "Default")
      (node (ref "LED1") (pin "A") (pinfunction "A_A") (pintype "passive"))
      (node (ref "R18") (pin "2") (pinfunction "2_2") (pintype "passive"))
    )
    (net (code "51") (name "Net-(LED_G-PadA)") (class "Default")
      (node (ref "LED_G") (pin "A") (pinfunction "A_A") (pintype "passive"))
      (node (ref "R23") (pin "1") (pinfunction "1_1") (pintype "passive"))
    )
    (net (code "52") (name "Net-(LED_R-PadA)") (class "Default")
      (node (ref "LED_R") (pin "A") (pinfunction "A_A") (pintype "passive"))
      (node (ref "R25") (pin "1") (pinfunction "1_1") (pintype "passive"))
    )
    (net (code "53") (name "Net-(MPU9150-CPOUT)") (class "Default")
      (node (ref "C23") (pin "1") (pinfunction "1_1") (pintype "passive"))
      (node (ref "MPU9150") (pin "20") (pinfunction "CPOUT_20") (pintype "bidirectional"))
    )
    (net (code "54") (name "Net-(MPU9150-E_SCL)") (class "Default")
      (node (ref "MPU9150") (pin "7") (pinfunction "E_SCL_7") (pintype "bidirectional"))
      (node (ref "MS5611") (pin "8") (pinfunction "SCLK_8") (pintype "input"))
      (node (ref "R40") (pin "1") (pinfunction "1_1") (pintype "passive"))
    )
    (net (code "55") (name "Net-(MPU9150-E_SDA)") (class "Default")
      (node (ref "MPU9150") (pin "6") (pinfunction "E_SDA_6") (pintype "bidirectional"))
      (node (ref "MS5611") (pin "7") (pinfunction "SDI/SDA_7") (pintype "bidirectional"))
      (node (ref "R39") (pin "2") (pinfunction "2_2") (pintype "passive"))
    )
    (net (code "56") (name "Net-(MPU9150-REGOUT)") (class "Default")
      (node (ref "C24") (pin "1") (pinfunction "1_1") (pintype "passive"))
      (node (ref "MPU9150") (pin "10") (pinfunction "REGOUT_10") (pintype "bidirectional"))
    )
    (net (code "57") (name "Net-(R1-Pad1)") (class "Default")
      (node (ref "R1") (pin "1") (pinfunction "1_1") (pintype "passive"))
      (node (ref "R2") (pin "1") (pinfunction "1_1") (pintype "passive"))
      (node (ref "SPORT") (pin "1") (pinfunction "1_1") (pintype "passive"))
    )
    (net (code "58") (name "Net-(R21-Pad1)") (class "Default")
      (node (ref "R21") (pin "1") (pinfunction "1_1") (pintype "passive"))
      (node (ref "SBUS") (pin "1") (pinfunction "1_1") (pintype "passive"))
    )
    (net (code "59") (name "Net-(RFM95-ANT)") (class "Default")
      (node (ref "RFM95") (pin "9") (pinfunction "ANT_9") (pintype "bidirectional"))
      (node (ref "X1") (pin "P") (pinfunction "ANT_P") (pintype "bidirectional"))
    )
    (net (code "60") (name "Net-(STM32F103RET6H-PD0{slash}OSC<=)") (class "Default")
      (node (ref "C1") (pin "1") (pinfunction "1_1") (pintype "passive"))
      (node (ref "STM32F103RET6") (pin "5") (pinfunction "PD0/OSC<=_5") (pintype "bidirectional"))
      (node (ref "Y1") (pin "3") (pinfunction "2_3") (pintype "passive"))
    )
    (net (code "61") (name "Net-(STM32F103RET6H-PD1{slash}OSC=>)") (class "Default")
      (node (ref "R5") (pin "1") (pinfunction "1_1") (pintype "passive"))
      (node (ref "STM32F103RET6") (pin "6") (pinfunction "PD1/OSC=>_6") (pintype "bidirectional"))
    )
    (net (code "62") (name "Net-(STM32F103RET6J-BOOT0)") (class "Default")
      (node (ref "R8") (pin "1") (pinfunction "1_1") (pintype "passive"))
      (node (ref "STM32F103RET6") (pin "60") (pinfunction "BOOT0_60") (pintype "input"))
    )
    (net (code "63") (name "Net-(STM32F103RET6J-NRST)") (class "Default")
      (node (ref "R9") (pin "2") (pinfunction "2_2") (pintype "passive"))
      (node (ref "STM32F103RET6") (pin "7") (pinfunction "NRST_7") (pintype "input"))
    )
    (net (code "64") (name "SPI1_MISO") (class "Default")
      (node (ref "NRF24L01_SMD") (pin "P$3") (pinfunction "MISO_P$3") (pintype "output"))
      (node (ref "STM32F103RET6") (pin "22") (pinfunction "PA6_22") (pintype "bidirectional"))
    )
    (net (code "65") (name "SPI1_MOSI") (class "Default")
      (node (ref "NRF24L01_SMD") (pin "P$4") (pinfunction "MOSI_P$4") (pintype "input"))
      (node (ref "STM32F103RET6") (pin "23") (pinfunction "PA7_23") (pintype "bidirectional"))
    )
    (net (code "66") (name "SPI1_SCK") (class "Default")
      (node (ref "NRF24L01_SMD") (pin "P$5") (pinfunction "SCK_P$5") (pintype "input"))
      (node (ref "STM32F103RET6") (pin "21") (pinfunction "PA5_21") (pintype "bidirectional"))
    )
    (net (code "67") (name "SPI2_MISO") (class "Default")
      (node (ref "RFM95") (pin "2") (pinfunction "MISO_2") (pintype "output"))
      (node (ref "STM32F103RET6") (pin "35") (pinfunction "PB14_35") (pintype "bidirectional"))
    )
    (net (code "68") (name "SPI2_MOSI") (class "Default")
      (node (ref "RFM95") (pin "3") (pinfunction "MOSI_3") (pintype "input"))
      (node (ref "STM32F103RET6") (pin "36") (pinfunction "PB15_36") (pintype "bidirectional"))
    )
    (net (code "69") (name "SPI2_SCK") (class "Default")
      (node (ref "RFM95") (pin "4") (pinfunction "SCK_4") (pintype "input"))
      (node (ref "STM32F103RET6") (pin "34") (pinfunction "PB13_34") (pintype "bidirectional"))
    )
    (net (code "70") (name "SWCLK") (class "Default")
      (node (ref "D2") (pin "C") (pinfunction "C_C") (pintype "passive"))
      (node (ref "STM32F103RET6") (pin "49") (pinfunction "PA14_49") (pintype "bidirectional"))
      (node (ref "SWD") (pin "2") (pinfunction "2_2") (pintype "passive"))
    )
    (net (code "71") (name "SWDIO") (class "Default")
      (node (ref "D1") (pin "C") (pinfunction "C_C") (pintype "passive"))
      (node (ref "STM32F103RET6") (pin "46") (pinfunction "PA13_46") (pintype "bidirectional"))
      (node (ref "SWD") (pin "4") (pinfunction "4_4") (pintype "passive"))
    )
    (net (code "72") (name "USART1_CK") (class "Default")
      (node (ref "STM32F103RET6") (pin "41") (pinfunction "PA8_41") (pintype "bidirectional"))
    )
    (net (code "73") (name "USART1_RX") (class "Default")
      (node (ref "2N2222_RX") (pin "C") (pinfunction "C_C") (pintype "passive"))
      (node (ref "R17") (pin "2") (pinfunction "2_2") (pintype "passive"))
      (node (ref "STM32F103RET6") (pin "43") (pinfunction "PA10_43") (pintype "bidirectional"))
    )
    (net (code "74") (name "USART1_TX") (class "Default")
      (node (ref "R12") (pin "2") (pinfunction "2_2") (pintype "passive"))
      (node (ref "STM32F103RET6") (pin "42") (pinfunction "PA9_42") (pintype "bidirectional"))
    )
    (net (code "75") (name "USART3_RX") (class "Default")
      (node (ref "STM32F103RET6") (pin "52") (pinfunction "PC11_52") (pintype "bidirectional"))
    )
    (net (code "76") (name "USART3_TX") (class "Default")
      (node (ref "2N2222_TX1") (pin "B") (pinfunction "B_B") (pintype "passive"))
      (node (ref "STM32F103RET6") (pin "51") (pinfunction "PC10_51") (pintype "bidirectional"))
    )
    (net (code "77") (name "V+") (class "Default")
      (node (ref "BAT60JFILM") (pin "A") (pinfunction "A_A") (pintype "passive"))
      (node (ref "C20") (pin "1") (pinfunction "1_1") (pintype "passive"))
      (node (ref "C21") (pin "1") (pinfunction "1_1") (pintype "passive"))
      (node (ref "C22") (pin "1") (pinfunction "1_1") (pintype "passive"))
      (node (ref "C5") (pin "+") (pinfunction "+_+") (pintype "passive"))
      (node (ref "C7") (pin "1") (pinfunction "1_1") (pintype "passive"))
      (node (ref "CH0") (pin "2") (pinfunction "2_2") (pintype "passive"))
      (node (ref "CH1") (pin "2") (pinfunction "2_2") (pintype "passive"))
      (node (ref "CH10") (pin "2") (pinfunction "2_2") (pintype "passive"))
      (node (ref "CH11") (pin "2") (pinfunction "2_2") (pintype "passive"))
      (node (ref "CH2") (pin "2") (pinfunction "2_2") (pintype "passive"))
      (node (ref "CH3") (pin "2") (pinfunction "2_2") (pintype "passive"))
      (node (ref "CH4") (pin "2") (pinfunction "2_2") (pintype "passive"))
      (node (ref "CH5") (pin "2") (pinfunction "2_2") (pintype "passive"))
      (node (ref "CH6") (pin "2") (pinfunction "2_2") (pintype "passive"))
      (node (ref "CH7") (pin "2") (pinfunction "2_2") (pintype "passive"))
      (node (ref "CH8") (pin "2") (pinfunction "2_2") (pintype "passive"))
      (node (ref "CH9") (pin "2") (pinfunction "2_2") (pintype "passive"))
      (node (ref "SBUS") (pin "2") (pinfunction "2_2") (pintype "passive"))
      (node (ref "SPORT") (pin "2") (pinfunction "2_2") (pintype "passive"))
    )
    (net (code "78") (name "VCC") (class "Default")
      (node (ref "C10") (pin "1") (pinfunction "1_1") (pintype "passive"))
      (node (ref "C11") (pin "1") (pinfunction "1_1") (pintype "passive"))
      (node (ref "C12") (pin "1") (pinfunction "1_1") (pintype "passive"))
      (node (ref "C13") (pin "1") (pinfunction "1_1") (pintype "passive"))
      (node (ref "C14") (pin "1") (pinfunction "1_1") (pintype "passive"))
      (node (ref "C15") (pin "1") (pinfunction "1_1") (pintype "passive"))
      (node (ref "C16") (pin "1") (pinfunction "1_1") (pintype "passive"))
      (node (ref "C17") (pin "1") (pinfunction "1_1") (pintype "passive"))
      (node (ref "C18") (pin "1") (pinfunction "1_1") (pintype "passive"))
      (node (ref "C25") (pin "1") (pinfunction "1_1") (pintype "passive"))
      (node (ref "C3") (pin "1") (pinfunction "1_1") (pintype "passive"))
      (node (ref "C4") (pin "2") (pinfunction "2_2") (pintype "passive"))
      (node (ref "C6") (pin "1") (pinfunction "1_1") (pintype "passive"))
      (node (ref "FCM1608-0603") (pin "1") (pinfunction "P$1_1") (pintype "bidirectional"))
      (node (ref "IC1") (pin "2") (pinfunction "VOUT_2") (pintype "power_in"))
      (node (ref "IC1") (pin "4") (pinfunction "VOUT_4") (pintype "power_in"))
      (node (ref "MPU9150") (pin "13") (pinfunction "VDD_13") (pintype "bidirectional"))
      (node (ref "MPU9150") (pin "3") (pinfunction "VDD_3") (pintype "bidirectional"))
      (node (ref "MPU9150") (pin "8") (pinfunction "VLOGIC_8") (pintype "bidirectional"))
      (node (ref "MS5611") (pin "1") (pinfunction "VDD_1") (pintype "power_in"))
      (node (ref "MS5611") (pin "2") (pinfunction "PS_2") (pintype "input"))
      (node (ref "NRF24L01_SMD") (pin "P$8") (pinfunction "VDD_P$8") (pintype "bidirectional"))
      (node (ref "R10") (pin "1") (pinfunction "1_1") (pintype "passive"))
      (node (ref "R11") (pin "2") (pinfunction "2_2") (pintype "passive"))
      (node (ref "R17") (pin "1") (pinfunction "1_1") (pintype "passive"))
      (node (ref "R18") (pin "1") (pinfunction "1_1") (pintype "passive"))
      (node (ref "R20") (pin "2") (pinfunction "2_2") (pintype "passive"))
      (node (ref "R22") (pin "1") (pinfunction "1_1") (pintype "passive"))
      (node (ref "R3") (pin "1") (pinfunction "1_1") (pintype "passive"))
      (node (ref "R39") (pin "1") (pinfunction "1_1") (pintype "passive"))
      (node (ref "R40") (pin "2") (pinfunction "2_2") (pintype "passive"))
      (node (ref "R9") (pin "1") (pinfunction "1_1") (pintype "passive"))
      (node (ref "RFM95") (pin "13") (pinfunction "VCC_13") (pintype "bidirectional"))
      (node (ref "STM32F103RET6") (pin "1") (pinfunction "VBAT_1") (pintype "power_in"))
      (node (ref "STM32F103RET6") (pin "19") (pinfunction "VDD_4_19") (pintype "power_in"))
      (node (ref "STM32F103RET6") (pin "32") (pinfunction "VDD_1_32") (pintype "power_in"))
      (node (ref "STM32F103RET6") (pin "48") (pinfunction "VDD_2_48") (pintype "power_in"))
      (node (ref "STM32F103RET6") (pin "64") (pinfunction "VDD_3_64") (pintype "power_in"))
      (node (ref "SWD") (pin "1") (pinfunction "1_1") (pintype "passive"))
    )
    (net (code "79") (name "VDD") (class "Default")
      (node (ref "BAT60JFILM") (pin "C") (pinfunction "C_C") (pintype "passive"))
      (node (ref "IC1") (pin "3") (pinfunction "VIN_3") (pintype "input"))
    )
    (net (code "80") (name "unconnected-(MPU9150-CLKOUT-Pad22)") (class "Default")
      (node (ref "MPU9150") (pin "22") (pinfunction "CLKOUT_22") (pintype "bidirectional"))
    )
    (net (code "81") (name "unconnected-(MS5611-SDO-Pad6)") (class "Default")
      (node (ref "MS5611") (pin "6") (pinfunction "SDO_6") (pintype "output"))
    )
    (net (code "82") (name "unconnected-(STM32F103RET6C-PA4-Pad20)") (class "Default")
      (node (ref "STM32F103RET6") (pin "20") (pinfunction "PA4_20") (pintype "bidirectional"))
    )
    (net (code "83") (name "unconnected-(STM32F103RET6E-PB3-Pad55)") (class "Default")
      (node (ref "STM32F103RET6") (pin "55") (pinfunction "PB3_55") (pintype "bidirectional"))
    )
    (net (code "84") (name "unconnected-(STM32F103RET6F-PC13-Pad2)") (class "Default")
      (node (ref "STM32F103RET6") (pin "2") (pinfunction "PC13_2") (pintype "bidirectional"))
    )
    (net (code "85") (name "unconnected-(STM32F103RET6F-PC14-Pad3)") (class "Default")
      (node (ref "STM32F103RET6") (pin "3") (pinfunction "PC14_3") (pintype "bidirectional"))
    )
    (net (code "86") (name "unconnected-(STM32F103RET6F-PC15-Pad4)") (class "Default")
      (node (ref "STM32F103RET6") (pin "4") (pinfunction "PC15_4") (pintype "bidirectional"))
    )
    (net (code "87") (name "unconnected-(STM32F103RET6H-PD2-Pad54)") (class "Default")
      (node (ref "STM32F103RET6") (pin "54") (pinfunction "PD2_54") (pintype "bidirectional"))
    )
  )
)
